# Sensor.net
KiCad netlist of a schematic drawn in Altium Designer
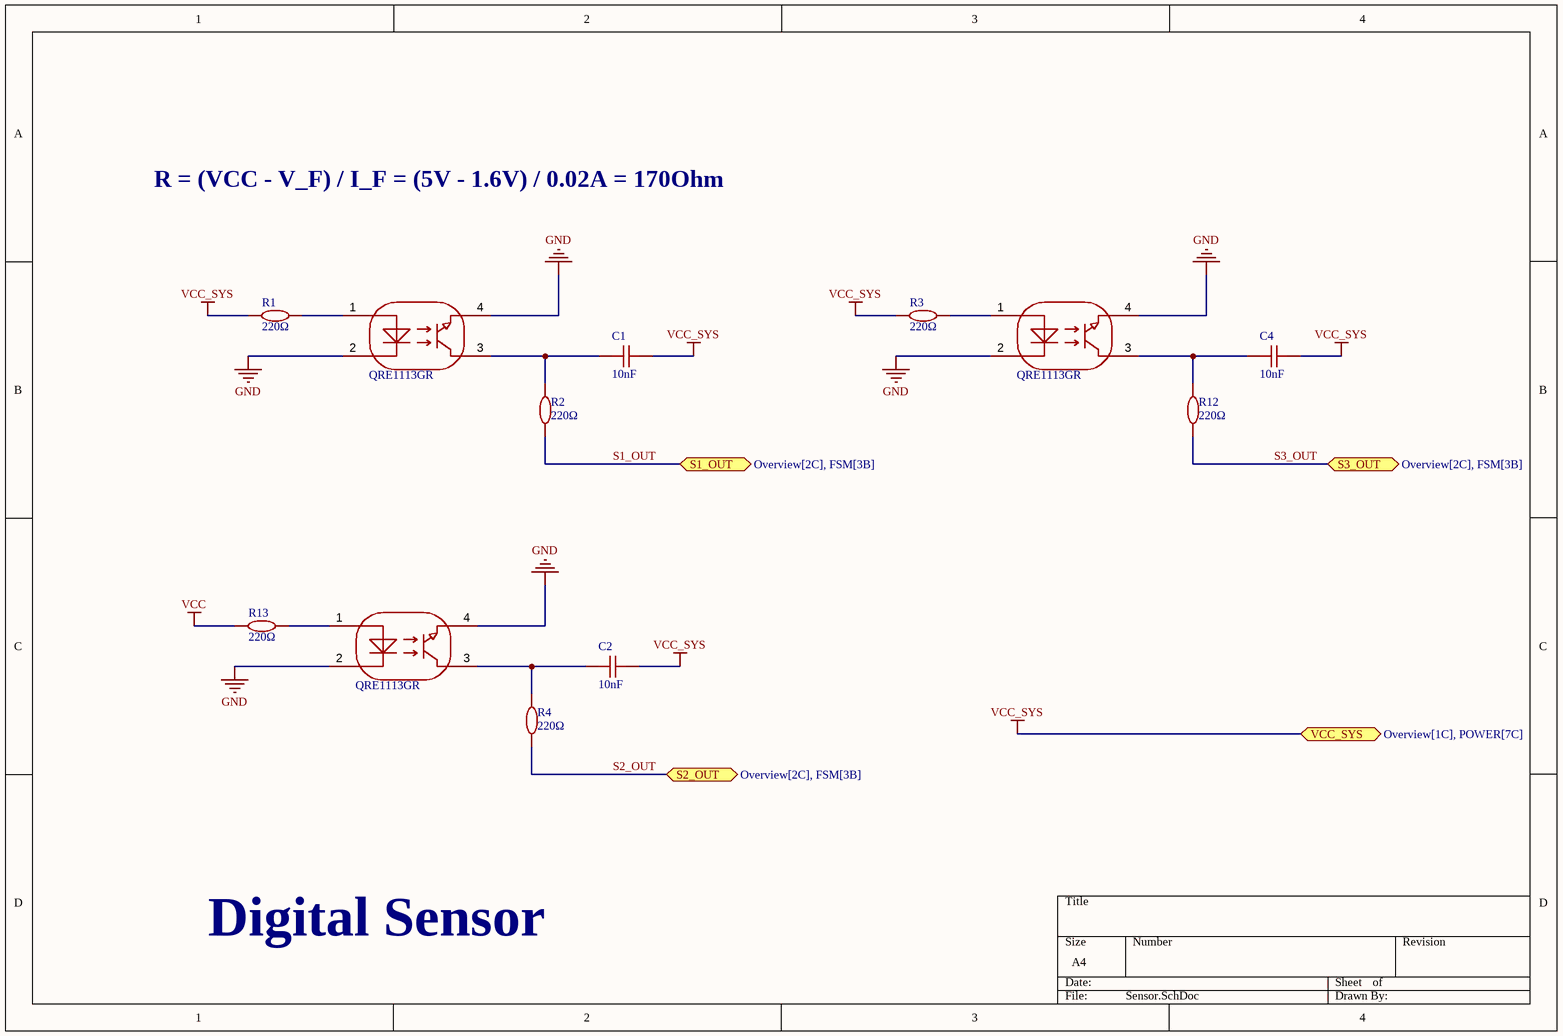
[diagram p0: Sensor.SchDoc]

(export (version "E")
  (design (tool "Eeschema 10.0.6"))
  (components
    (comp (ref "C1")
      (value "10nF")
      (footprint "C0402")
      (description "50V 10nF X7R ±10% 0402 Ceramic Capacitors ROHS")
      (libsource (lib "RLC") (part "10nF"))
    )
    (comp (ref "C2")
      (value "10nF")
      (footprint "C0402")
      (description "50V 10nF X7R ±10% 0402 Ceramic Capacitors ROHS")
      (libsource (lib "RLC") (part "10nF"))
    )
    (comp (ref "C4")
      (value "10nF")
      (footprint "C0402")
      (description "50V 10nF X7R ±10% 0402 Ceramic Capacitors ROHS")
      (libsource (lib "RLC") (part "10nF"))
    )
    (comp (ref "R1")
      (value "220Ω")
      (footprint "R0402")
      (description "100Ω 62.5mW 50V ±100ppm/℃ Thick Film Resistor ±1% 0402 Chip Resistor - Surface Mount ROHS")
      (libsource (lib "RLC") (part "100Ω"))
    )
    (comp (ref "R2")
      (value "220Ω")
      (footprint "R0402")
      (description "小尺寸、重量轻。降低组装成本,与贴片机匹配。适用于波峰焊和回流焊")
      (libsource (lib "RLC") (part "220Ω"))
    )
    (comp (ref "R3")
      (value "220Ω")
      (footprint "R0402")
      (description "100Ω 62.5mW 50V ±100ppm/℃ Thick Film Resistor ±1% 0402 Chip Resistor - Surface Mount ROHS")
      (libsource (lib "RLC") (part "100Ω"))
    )
    (comp (ref "R4")
      (value "220Ω")
      (footprint "R0402")
      (description "小尺寸、重量轻。降低组装成本,与贴片机匹配。适用于波峰焊和回流焊")
      (libsource (lib "RLC") (part "220Ω"))
    )
    (comp (ref "R12")
      (value "220Ω")
      (footprint "R0402")
      (description "小尺寸、重量轻。降低组装成本,与贴片机匹配。适用于波峰焊和回流焊")
      (libsource (lib "RLC") (part "220Ω"))
    )
    (comp (ref "R13")
      (value "220Ω")
      (footprint "R0402")
      (description "100Ω 62.5mW 50V ±100ppm/℃ Thick Film Resistor ±1% 0402 Chip Resistor - Surface Mount ROHS")
      (libsource (lib "RLC") (part "100Ω"))
    )
    (comp (ref "U1")
      (value "QRE1113GR")
      (footprint "OPTO-SMD_QRE1113GR")
      (description "QRE1113 由在塑料矩形盒体中与兼容硅光电晶体管并排封装的 940nm 发射极组成。采用表面贴装和通孔选项。")
      (libsource (lib "IC") (part "QRE1113GR"))
    )
    (comp (ref "U2")
      (value "QRE1113GR")
      (footprint "OPTO-SMD_QRE1113GR")
      (description "QRE1113 由在塑料矩形盒体中与兼容硅光电晶体管并排封装的 940nm 发射极组成。采用表面贴装和通孔选项。")
      (libsource (lib "IC") (part "QRE1113GR"))
    )
    (comp (ref "U3")
      (value "QRE1113GR")
      (footprint "OPTO-SMD_QRE1113GR")
      (description "QRE1113 由在塑料矩形盒体中与兼容硅光电晶体管并排封装的 940nm 发射极组成。采用表面贴装和通孔选项。")
      (libsource (lib "IC") (part "QRE1113GR"))
    )
  )
  (nets
    (net (code "1") (name "/S1_OUT") (class "Default")
      (node (ref "R2") (pin "1") (pinfunction "1_1") (pintype "passive"))
    )
    (net (code "2") (name "/S2_OUT") (class "Default")
      (node (ref "R4") (pin "1") (pinfunction "1_1") (pintype "passive"))
    )
    (net (code "3") (name "/S3_OUT") (class "Default")
      (node (ref "R12") (pin "1") (pinfunction "1_1") (pintype "passive"))
    )
    (net (code "4") (name "GND") (class "Default")
      (node (ref "U1") (pin "2") (pinfunction "2_2") (pintype "passive"))
      (node (ref "U1") (pin "4") (pinfunction "4_4") (pintype "passive"))
      (node (ref "U2") (pin "2") (pinfunction "2_2") (pintype "passive"))
      (node (ref "U2") (pin "4") (pinfunction "4_4") (pintype "passive"))
      (node (ref "U3") (pin "2") (pinfunction "2_2") (pintype "passive"))
      (node (ref "U3") (pin "4") (pinfunction "4_4") (pintype "passive"))
    )
    (net (code "5") (name "Net-(C1-Pad1)") (class "Default")
      (node (ref "C1") (pin "1") (pinfunction "1_1") (pintype "passive"))
      (node (ref "R2") (pin "2") (pinfunction "2_2") (pintype "passive"))
      (node (ref "U1") (pin "3") (pinfunction "3_3") (pintype "passive"))
    )
    (net (code "6") (name "Net-(C2-Pad1)") (class "Default")
      (node (ref "C2") (pin "1") (pinfunction "1_1") (pintype "passive"))
      (node (ref "R4") (pin "2") (pinfunction "2_2") (pintype "passive"))
      (node (ref "U2") (pin "3") (pinfunction "3_3") (pintype "passive"))
    )
    (net (code "7") (name "Net-(C4-Pad1)") (class "Default")
      (node (ref "C4") (pin "1") (pinfunction "1_1") (pintype "passive"))
      (node (ref "R12") (pin "2") (pinfunction "2_2") (pintype "passive"))
      (node (ref "U3") (pin "3") (pinfunction "3_3") (pintype "passive"))
    )
    (net (code "8") (name "Net-(R1-Pad1)") (class "Default")
      (node (ref "R1") (pin "1") (pinfunction "1_1") (pintype "passive"))
      (node (ref "U1") (pin "1") (pinfunction "1_1") (pintype "passive"))
    )
    (net (code "9") (name "Net-(R3-Pad1)") (class "Default")
      (node (ref "R3") (pin "1") (pinfunction "1_1") (pintype "passive"))
      (node (ref "U3") (pin "1") (pinfunction "1_1") (pintype "passive"))
    )
    (net (code "10") (name "Net-(R13-Pad1)") (class "Default")
      (node (ref "R13") (pin "1") (pinfunction "1_1") (pintype "passive"))
      (node (ref "U2") (pin "1") (pinfunction "1_1") (pintype "passive"))
    )
    (net (code "11") (name "VCC") (class "Default")
      (node (ref "R13") (pin "2") (pinfunction "2_2") (pintype "passive"))
    )
    (net (code "12") (name "VCC_SYS") (class "Default")
      (node (ref "C1") (pin "2") (pinfunction "2_2") (pintype "passive"))
      (node (ref "C2") (pin "2") (pinfunction "2_2") (pintype "passive"))
      (node (ref "C4") (pin "2") (pinfunction "2_2") (pintype "passive"))
      (node (ref "R1") (pin "2") (pinfunction "2_2") (pintype "passive"))
      (node (ref "R3") (pin "2") (pinfunction "2_2") (pintype "passive"))
    )
  )
)
